# opd_tester.net
KiCad netlist of a schematic drawn in EAGLE
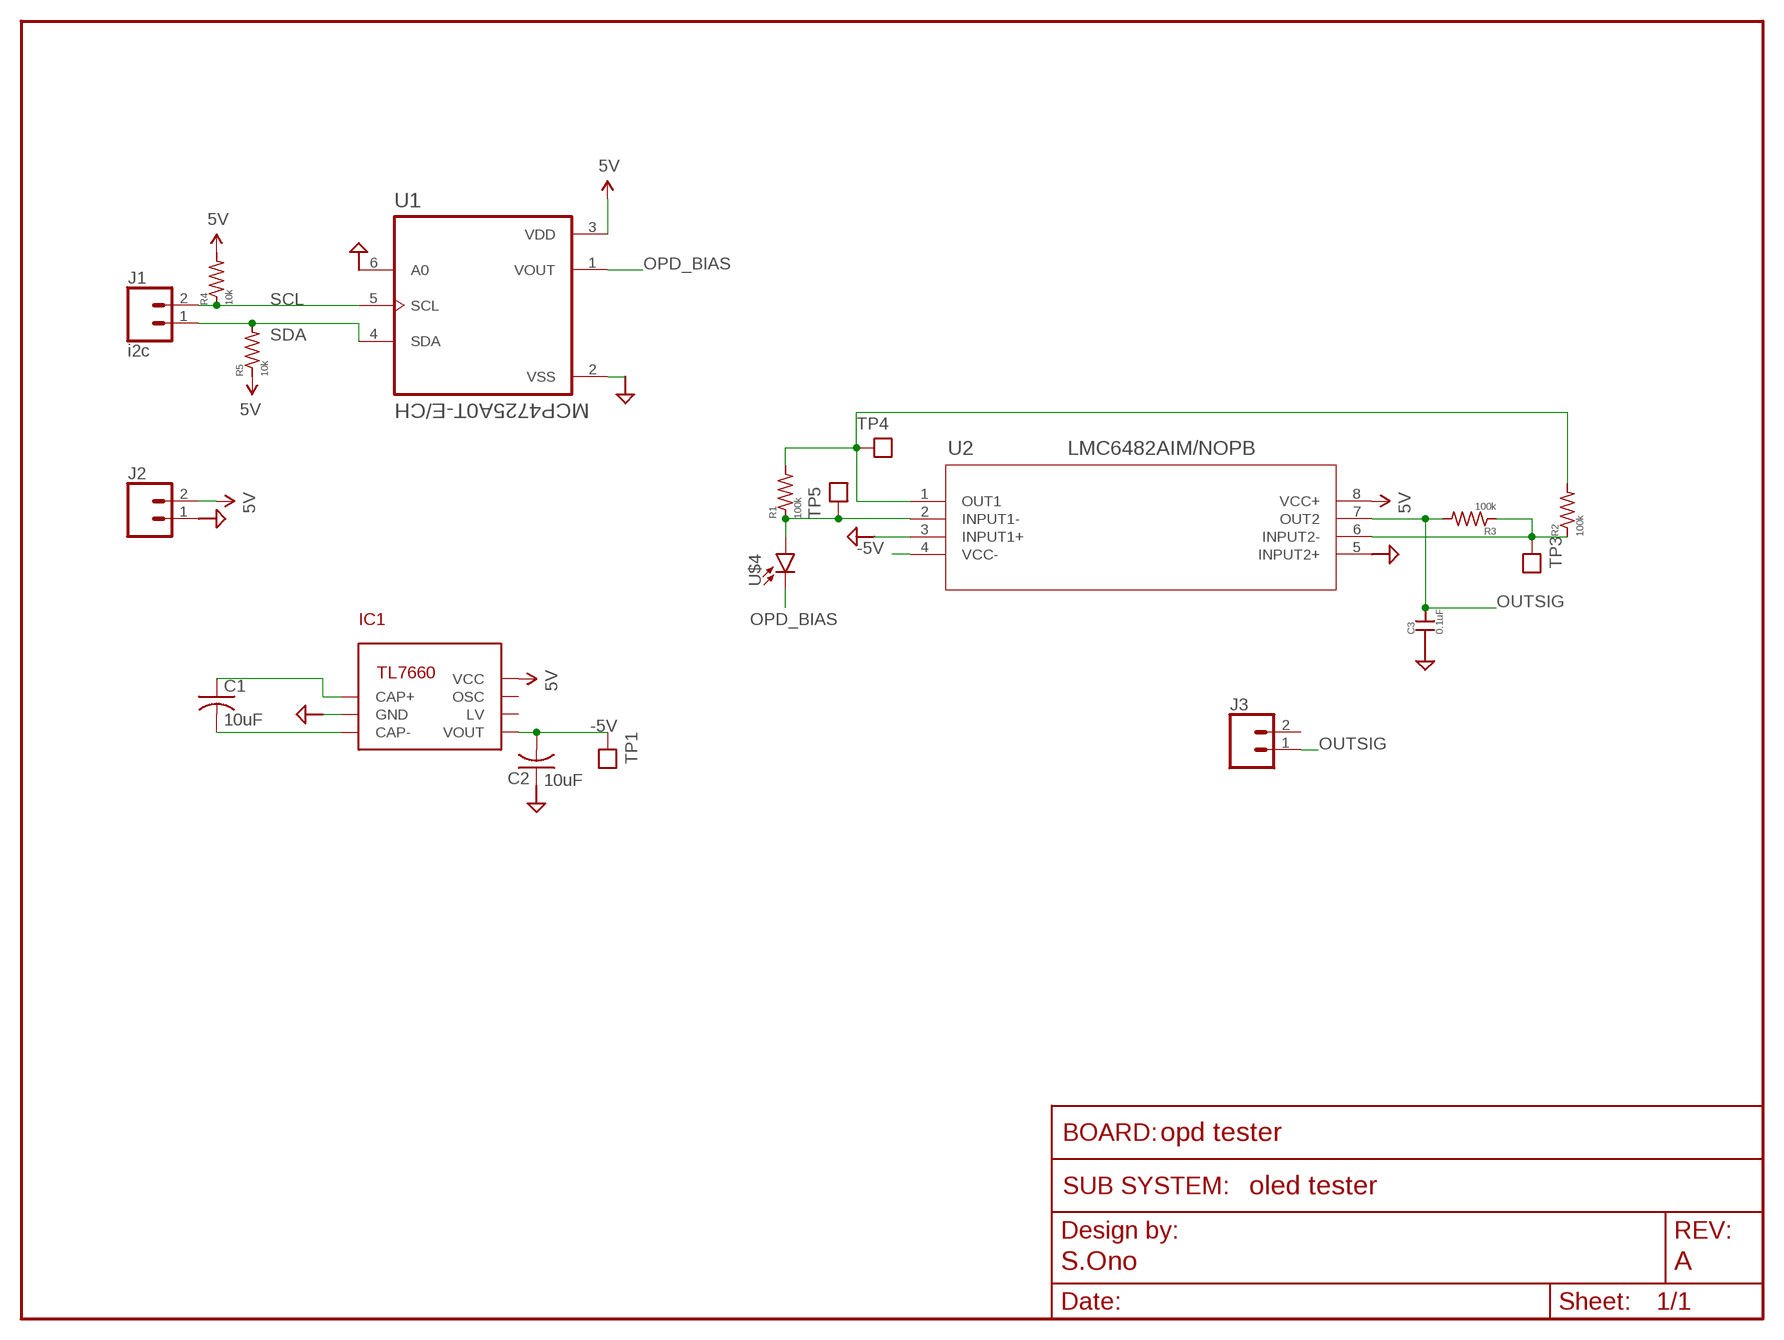
[diagram p0: schematic, sheet 1]

(export (version "E")
  (design (tool "Eeschema 10.0.6"))
  (components
    (comp (ref "C1")
      (value "10uF")
      (footprint "eagle-import:CAP_3MM")
      (libsource (lib "eagle-import") (part "CAP_ELEC_3MM_SMD"))
    )
    (comp (ref "C2")
      (value "10uF")
      (footprint "eagle-import:CAP_3MM")
      (libsource (lib "eagle-import") (part "CAP_ELEC_3MM_SMD"))
    )
    (comp (ref "C3")
      (value "0.1uF")
      (footprint "eagle-import:0603-CAP")
      (libsource (lib "eagle-import") (part "CAP0603-CAP"))
    )
    (comp (ref "IC1")
      (value "TL7660")
      (footprint "eagle-import:8SOICW")
      (libsource (lib "eagle-import") (part "TL7660"))
    )
    (comp (ref "J1")
      (value "i2c")
      (footprint "eagle-import:1X02")
      (libsource (lib "eagle-import") (part "CONN_02"))
    )
    (comp (ref "J2")
      (value "CONN_02")
      (footprint "eagle-import:1X02")
      (libsource (lib "eagle-import") (part "CONN_02"))
    )
    (comp (ref "J3")
      (value "CONN_02")
      (footprint "eagle-import:1X02")
      (libsource (lib "eagle-import") (part "CONN_02"))
    )
    (comp (ref "R1")
      (value "100k")
      (footprint "eagle-import:0603-RES")
      (libsource (lib "eagle-import") (part "R-US_0603"))
    )
    (comp (ref "R2")
      (value "100k")
      (footprint "eagle-import:0603-RES")
      (libsource (lib "eagle-import") (part "R-US_0603"))
    )
    (comp (ref "R3")
      (value "100k")
      (footprint "eagle-import:0603-RES")
      (libsource (lib "eagle-import") (part "R-US_0603"))
    )
    (comp (ref "R4")
      (value "10k")
      (footprint "eagle-import:0603-RES")
      (libsource (lib "eagle-import") (part "R-US_0603"))
    )
    (comp (ref "R5")
      (value "10k")
      (footprint "eagle-import:0603-RES")
      (libsource (lib "eagle-import") (part "R-US_0603"))
    )
    (comp (ref "TP1")
      (value "TEST_POINTTHRU")
      (footprint "eagle-import:TEST_POINT")
      (libsource (lib "eagle-import") (part "TEST_POINTTHRU"))
    )
    (comp (ref "TP3")
      (value "TEST_POINTTHRU")
      (footprint "eagle-import:TEST_POINT")
      (libsource (lib "eagle-import") (part "TEST_POINTTHRU"))
    )
    (comp (ref "TP4")
      (value "TEST_POINTTHRU")
      (footprint "eagle-import:TEST_POINT")
      (libsource (lib "eagle-import") (part "TEST_POINTTHRU"))
    )
    (comp (ref "TP5")
      (value "TEST_POINTTHRU")
      (footprint "eagle-import:TEST_POINT")
      (libsource (lib "eagle-import") (part "TEST_POINTTHRU"))
    )
    (comp (ref "U$4")
      (value "XDCR_SFH_229")
      (footprint "eagle-import:XDCR_SFH_229")
      (libsource (lib "eagle-import") (part "XDCR_SFH_229"))
    )
    (comp (ref "U1")
      (value "MCP4725A0T-E/CH")
      (footprint "eagle-import:SOT95P270X145-6N")
      (fields (field (name "DIGI-KEY_PART_NUMBER") "MCP4725A0T-E/CHCT-ND") (field (name "MF") "Microchip"))
      (libsource (lib "eagle-import") (part "MCP4725A0T-E/CH"))
    )
    (comp (ref "U2")
      (value "LMC6482AIM/NOPB")
      (footprint "eagle-import:M08A")
      (libsource (lib "eagle-import") (part "LMC6482AIM/NOPB"))
    )
  )
  (nets
    (net (code "1") (name "/-5V") (class "Default")
      (node (ref "C2") (pin "NEG") (pinfunction "NEG_NEG") (pintype "passive"))
      (node (ref "IC1") (pin "5") (pinfunction "VOUT_5") (pintype "bidirectional"))
      (node (ref "TP1") (pin "1") (pinfunction "P$1_1") (pintype "bidirectional"))
      (node (ref "U2") (pin "4") (pinfunction "VCC-_4") (pintype "passive"))
    )
    (net (code "2") (name "/OPD_BIAS") (class "Default")
      (node (ref "U$4") (pin "2") (pinfunction "C_2") (pintype "passive"))
      (node (ref "U1") (pin "1") (pinfunction "VOUT_1") (pintype "output"))
    )
    (net (code "3") (name "/OUTSIG") (class "Default")
      (node (ref "C3") (pin "2") (pinfunction "2_2") (pintype "passive"))
      (node (ref "J3") (pin "1") (pinfunction "1_1") (pintype "passive"))
      (node (ref "R3") (pin "2") (pinfunction "2_2") (pintype "passive"))
      (node (ref "U2") (pin "7") (pinfunction "OUT2_7") (pintype "passive"))
    )
    (net (code "4") (name "/SCL") (class "Default")
      (node (ref "J1") (pin "2") (pinfunction "2_2") (pintype "passive"))
      (node (ref "R4") (pin "1") (pinfunction "1_1") (pintype "passive"))
      (node (ref "U1") (pin "5") (pinfunction "SCL_5") (pintype "input"))
    )
    (net (code "5") (name "/SDA") (class "Default")
      (node (ref "J1") (pin "1") (pinfunction "1_1") (pintype "passive"))
      (node (ref "R5") (pin "2") (pinfunction "2_2") (pintype "passive"))
      (node (ref "U1") (pin "4") (pinfunction "SDA_4") (pintype "bidirectional"))
    )
    (net (code "6") (name "5V") (class "Default")
      (node (ref "IC1") (pin "8") (pinfunction "VCC_8") (pintype "bidirectional"))
      (node (ref "J2") (pin "2") (pinfunction "2_2") (pintype "passive"))
      (node (ref "R4") (pin "2") (pinfunction "2_2") (pintype "passive"))
      (node (ref "R5") (pin "1") (pinfunction "1_1") (pintype "passive"))
      (node (ref "U1") (pin "3") (pinfunction "VDD_3") (pintype "power_in"))
      (node (ref "U2") (pin "8") (pinfunction "VCC+_8") (pintype "passive"))
    )
    (net (code "7") (name "GND") (class "Default")
      (node (ref "C2") (pin "POS") (pinfunction "POS_POS") (pintype "passive"))
      (node (ref "C3") (pin "1") (pinfunction "1_1") (pintype "passive"))
      (node (ref "IC1") (pin "3") (pinfunction "GND_3") (pintype "bidirectional"))
      (node (ref "J2") (pin "1") (pinfunction "1_1") (pintype "passive"))
      (node (ref "U1") (pin "2") (pinfunction "VSS_2") (pintype "power_in"))
      (node (ref "U1") (pin "6") (pinfunction "A0_6") (pintype "input"))
      (node (ref "U2") (pin "3") (pinfunction "INPUT1+_3") (pintype "passive"))
      (node (ref "U2") (pin "5") (pinfunction "INPUT2+_5") (pintype "passive"))
    )
    (net (code "8") (name "Net-(IC1-CAP+)") (class "Default")
      (node (ref "C1") (pin "POS") (pinfunction "POS_POS") (pintype "passive"))
      (node (ref "IC1") (pin "2") (pinfunction "CAP+_2") (pintype "bidirectional"))
    )
    (net (code "9") (name "Net-(IC1-CAP-)") (class "Default")
      (node (ref "C1") (pin "NEG") (pinfunction "NEG_NEG") (pintype "passive"))
      (node (ref "IC1") (pin "4") (pinfunction "CAP-_4") (pintype "bidirectional"))
    )
    (net (code "10") (name "Net-(TP3-P$1)") (class "Default")
      (node (ref "R2") (pin "1") (pinfunction "1_1") (pintype "passive"))
      (node (ref "R3") (pin "1") (pinfunction "1_1") (pintype "passive"))
      (node (ref "TP3") (pin "1") (pinfunction "P$1_1") (pintype "bidirectional"))
      (node (ref "U2") (pin "6") (pinfunction "INPUT2-_6") (pintype "passive"))
    )
    (net (code "11") (name "Net-(TP4-P$1)") (class "Default")
      (node (ref "R1") (pin "2") (pinfunction "2_2") (pintype "passive"))
      (node (ref "R2") (pin "2") (pinfunction "2_2") (pintype "passive"))
      (node (ref "TP4") (pin "1") (pinfunction "P$1_1") (pintype "bidirectional"))
      (node (ref "U2") (pin "1") (pinfunction "OUT1_1") (pintype "passive"))
    )
    (net (code "12") (name "Net-(TP5-P$1)") (class "Default")
      (node (ref "R1") (pin "1") (pinfunction "1_1") (pintype "passive"))
      (node (ref "TP5") (pin "1") (pinfunction "P$1_1") (pintype "bidirectional"))
      (node (ref "U$4") (pin "1") (pinfunction "A_1") (pintype "passive"))
      (node (ref "U2") (pin "2") (pinfunction "INPUT1-_2") (pintype "passive"))
    )
    (net (code "13") (name "unconnected-(IC1-LV-Pad6)") (class "Default")
      (node (ref "IC1") (pin "6") (pinfunction "LV_6") (pintype "bidirectional"))
    )
    (net (code "14") (name "unconnected-(IC1-OSC-Pad7)") (class "Default")
      (node (ref "IC1") (pin "7") (pinfunction "OSC_7") (pintype "bidirectional"))
    )
    (net (code "15") (name "unconnected-(J3-Pad2)") (class "Default")
      (node (ref "J3") (pin "2") (pinfunction "2_2") (pintype "passive"))
    )
  )
)
